# SubHarmonics_Control_Board_v1.net
KiCad netlist of a schematic drawn in EAGLE
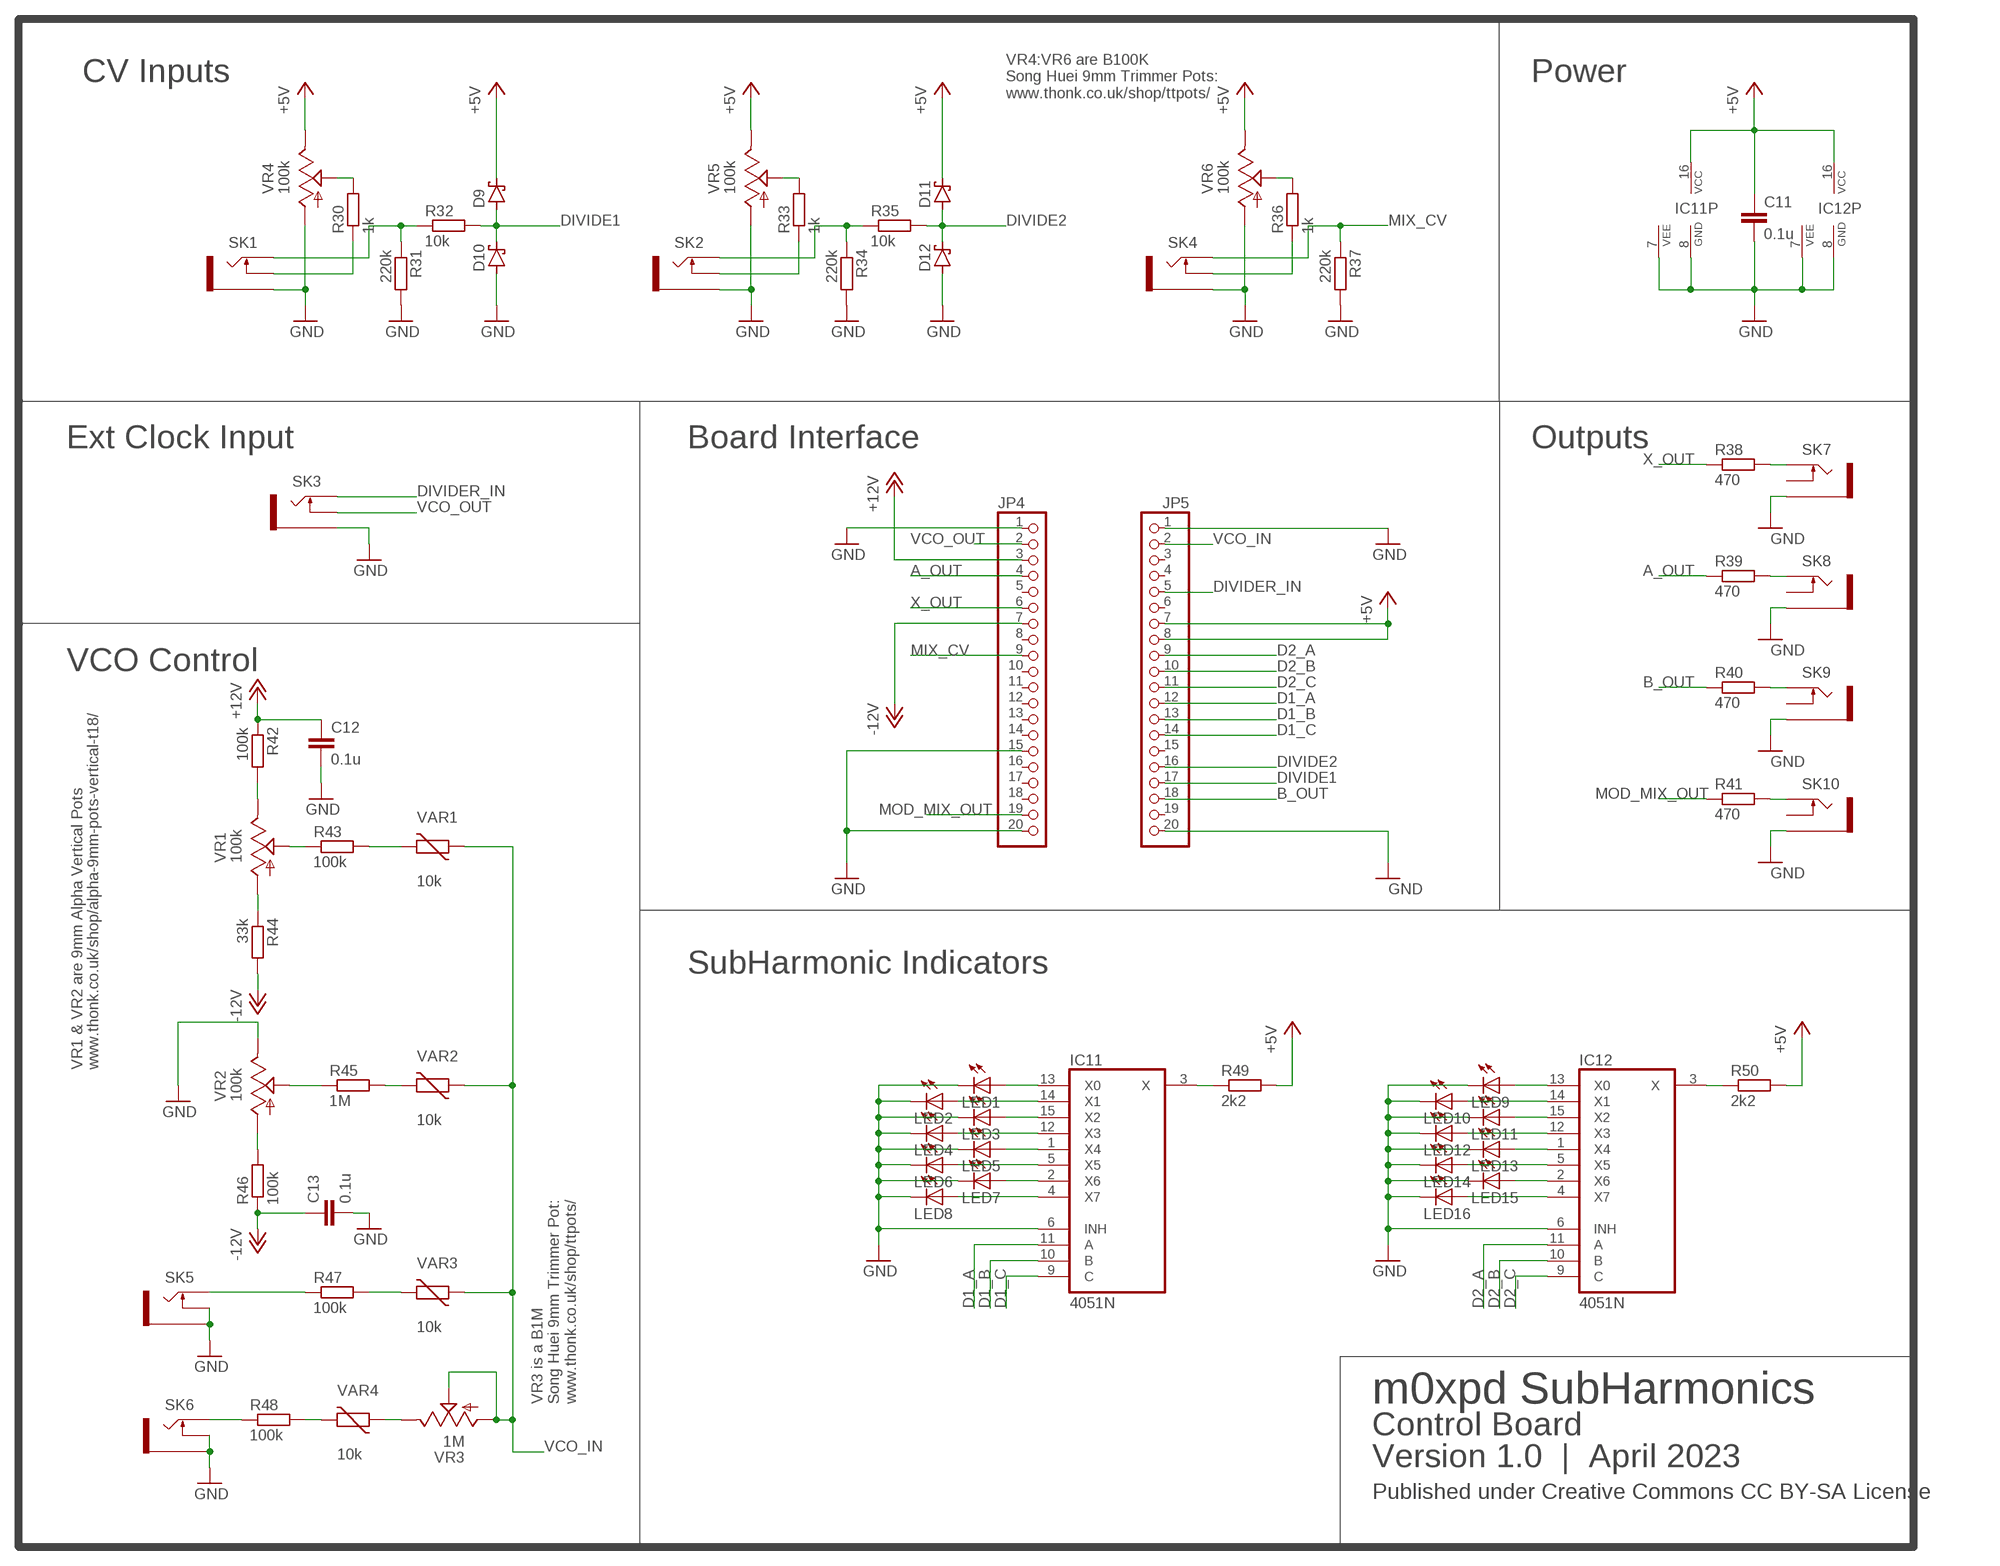
[diagram p0: schematic, sheet 1]

(export (version "E")
  (design (tool "Eeschema 10.0.6"))
  (components
    (comp (ref "C11")
      (value "0.1u")
      (footprint "eagle-import:C050-025X075")
      (libsource (lib "eagle-import") (part "C-EU050-025X075"))
    )
    (comp (ref "C12")
      (value "0.1u")
      (footprint "eagle-import:C050-025X075")
      (libsource (lib "eagle-import") (part "C-EU050-025X075"))
    )
    (comp (ref "C13")
      (value "0.1u")
      (footprint "eagle-import:C050-025X075")
      (libsource (lib "eagle-import") (part "C-EU050-025X075"))
    )
    (comp (ref "D9")
      (value "1N5817-T")
      (footprint "eagle-import:DO41-7.6")
      (libsource (lib "eagle-import") (part "1N5817-T"))
    )
    (comp (ref "D10")
      (value "1N5817-T")
      (footprint "eagle-import:DO41-7.6")
      (libsource (lib "eagle-import") (part "1N5817-T"))
    )
    (comp (ref "D11")
      (value "1N5817-T")
      (footprint "eagle-import:DO41-7.6")
      (libsource (lib "eagle-import") (part "1N5817-T"))
    )
    (comp (ref "D12")
      (value "1N5817-T")
      (footprint "eagle-import:DO41-7.6")
      (libsource (lib "eagle-import") (part "1N5817-T"))
    )
    (comp (ref "IC11")
      (value "4051N")
      (footprint "eagle-import:DIL16")
      (libsource (lib "eagle-import") (part "4051N"))
    )
    (comp (ref "IC12")
      (value "4051N")
      (footprint "eagle-import:DIL16")
      (libsource (lib "eagle-import") (part "4051N"))
    )
    (comp (ref "JP4")
      (value "PINHD-1X20")
      (footprint "eagle-import:1X20")
      (libsource (lib "eagle-import") (part "PINHD-1X20"))
    )
    (comp (ref "JP5")
      (value "PINHD-1X20")
      (footprint "eagle-import:1X20")
      (libsource (lib "eagle-import") (part "PINHD-1X20"))
    )
    (comp (ref "LED1")
      (value "LED3MM")
      (footprint "eagle-import:LED3MM")
      (libsource (lib "eagle-import") (part "LED3MM"))
    )
    (comp (ref "LED2")
      (value "LED3MM")
      (footprint "eagle-import:LED3MM")
      (libsource (lib "eagle-import") (part "LED3MM"))
    )
    (comp (ref "LED3")
      (value "LED3MM")
      (footprint "eagle-import:LED3MM")
      (libsource (lib "eagle-import") (part "LED3MM"))
    )
    (comp (ref "LED4")
      (value "LED3MM")
      (footprint "eagle-import:LED3MM")
      (libsource (lib "eagle-import") (part "LED3MM"))
    )
    (comp (ref "LED5")
      (value "LED3MM")
      (footprint "eagle-import:LED3MM")
      (libsource (lib "eagle-import") (part "LED3MM"))
    )
    (comp (ref "LED6")
      (value "LED3MM")
      (footprint "eagle-import:LED3MM")
      (libsource (lib "eagle-import") (part "LED3MM"))
    )
    (comp (ref "LED7")
      (value "LED3MM")
      (footprint "eagle-import:LED3MM")
      (libsource (lib "eagle-import") (part "LED3MM"))
    )
    (comp (ref "LED8")
      (value "LED3MM")
      (footprint "eagle-import:LED3MM")
      (libsource (lib "eagle-import") (part "LED3MM"))
    )
    (comp (ref "LED9")
      (value "LED3MM")
      (footprint "eagle-import:LED3MM")
      (libsource (lib "eagle-import") (part "LED3MM"))
    )
    (comp (ref "LED10")
      (value "LED3MM")
      (footprint "eagle-import:LED3MM")
      (libsource (lib "eagle-import") (part "LED3MM"))
    )
    (comp (ref "LED11")
      (value "LED3MM")
      (footprint "eagle-import:LED3MM")
      (libsource (lib "eagle-import") (part "LED3MM"))
    )
    (comp (ref "LED12")
      (value "LED3MM")
      (footprint "eagle-import:LED3MM")
      (libsource (lib "eagle-import") (part "LED3MM"))
    )
    (comp (ref "LED13")
      (value "LED3MM")
      (footprint "eagle-import:LED3MM")
      (libsource (lib "eagle-import") (part "LED3MM"))
    )
    (comp (ref "LED14")
      (value "LED3MM")
      (footprint "eagle-import:LED3MM")
      (libsource (lib "eagle-import") (part "LED3MM"))
    )
    (comp (ref "LED15")
      (value "LED3MM")
      (footprint "eagle-import:LED3MM")
      (libsource (lib "eagle-import") (part "LED3MM"))
    )
    (comp (ref "LED16")
      (value "LED3MM")
      (footprint "eagle-import:LED3MM")
      (libsource (lib "eagle-import") (part "LED3MM"))
    )
    (comp (ref "R30")
      (value "1k")
      (footprint "eagle-import:0204_7")
      (libsource (lib "eagle-import") (part "R-EU_0204/7"))
    )
    (comp (ref "R31")
      (value "220k")
      (footprint "eagle-import:0204_7")
      (libsource (lib "eagle-import") (part "R-EU_0204/7"))
    )
    (comp (ref "R32")
      (value "10k")
      (footprint "eagle-import:0204_7")
      (libsource (lib "eagle-import") (part "R-EU_0204/7"))
    )
    (comp (ref "R33")
      (value "1k")
      (footprint "eagle-import:0204_7")
      (libsource (lib "eagle-import") (part "R-EU_0204/7"))
    )
    (comp (ref "R34")
      (value "220k")
      (footprint "eagle-import:0204_7")
      (libsource (lib "eagle-import") (part "R-EU_0204/7"))
    )
    (comp (ref "R35")
      (value "10k")
      (footprint "eagle-import:0204_7")
      (libsource (lib "eagle-import") (part "R-EU_0204/7"))
    )
    (comp (ref "R36")
      (value "1k")
      (footprint "eagle-import:0204_7")
      (libsource (lib "eagle-import") (part "R-EU_0204/7"))
    )
    (comp (ref "R37")
      (value "220k")
      (footprint "eagle-import:0204_7")
      (libsource (lib "eagle-import") (part "R-EU_0204/7"))
    )
    (comp (ref "R38")
      (value "470")
      (footprint "eagle-import:0204_7")
      (libsource (lib "eagle-import") (part "R-EU_0204/7"))
    )
    (comp (ref "R39")
      (value "470")
      (footprint "eagle-import:0204_7")
      (libsource (lib "eagle-import") (part "R-EU_0204/7"))
    )
    (comp (ref "R40")
      (value "470")
      (footprint "eagle-import:0204_7")
      (libsource (lib "eagle-import") (part "R-EU_0204/7"))
    )
    (comp (ref "R41")
      (value "470")
      (footprint "eagle-import:0204_7")
      (libsource (lib "eagle-import") (part "R-EU_0204/7"))
    )
    (comp (ref "R42")
      (value "100k")
      (footprint "eagle-import:0204_7")
      (libsource (lib "eagle-import") (part "R-EU_0204/7"))
    )
    (comp (ref "R43")
      (value "100k")
      (footprint "eagle-import:0204_7")
      (libsource (lib "eagle-import") (part "R-EU_0204/7"))
    )
    (comp (ref "R44")
      (value "33k")
      (footprint "eagle-import:0204_7")
      (libsource (lib "eagle-import") (part "R-EU_0204/7"))
    )
    (comp (ref "R45")
      (value "1M")
      (footprint "eagle-import:0204_7")
      (libsource (lib "eagle-import") (part "R-EU_0204/7"))
    )
    (comp (ref "R46")
      (value "100k")
      (footprint "eagle-import:0204_7")
      (libsource (lib "eagle-import") (part "R-EU_0204/7"))
    )
    (comp (ref "R47")
      (value "100k")
      (footprint "eagle-import:0204_7")
      (libsource (lib "eagle-import") (part "R-EU_0204/7"))
    )
    (comp (ref "R48")
      (value "100k")
      (footprint "eagle-import:0204_7")
      (libsource (lib "eagle-import") (part "R-EU_0204/7"))
    )
    (comp (ref "R49")
      (value "2k2")
      (footprint "eagle-import:0204_7")
      (libsource (lib "eagle-import") (part "R-EU_0204/7"))
    )
    (comp (ref "R50")
      (value "2k2")
      (footprint "eagle-import:0204_7")
      (libsource (lib "eagle-import") (part "R-EU_0204/7"))
    )
    (comp (ref "SK1")
      (value "THONKICONN_JACK")
      (footprint "eagle-import:WQP-PJ301M-12_JACK")
      (libsource (lib "eagle-import") (part "THONKICONN_JACK"))
    )
    (comp (ref "SK2")
      (value "THONKICONN_JACK")
      (footprint "eagle-import:WQP-PJ301M-12_JACK")
      (libsource (lib "eagle-import") (part "THONKICONN_JACK"))
    )
    (comp (ref "SK3")
      (value "THONKICONN_JACK")
      (footprint "eagle-import:WQP-PJ301M-12_JACK")
      (libsource (lib "eagle-import") (part "THONKICONN_JACK"))
    )
    (comp (ref "SK4")
      (value "THONKICONN_JACK")
      (footprint "eagle-import:WQP-PJ301M-12_JACK")
      (libsource (lib "eagle-import") (part "THONKICONN_JACK"))
    )
    (comp (ref "SK5")
      (value "THONKICONN_JACK")
      (footprint "eagle-import:WQP-PJ301M-12_JACK")
      (libsource (lib "eagle-import") (part "THONKICONN_JACK"))
    )
    (comp (ref "SK6")
      (value "THONKICONN_JACK")
      (footprint "eagle-import:WQP-PJ301M-12_JACK")
      (libsource (lib "eagle-import") (part "THONKICONN_JACK"))
    )
    (comp (ref "SK7")
      (value "THONKICONN_JACK")
      (footprint "eagle-import:WQP-PJ301M-12_JACK")
      (libsource (lib "eagle-import") (part "THONKICONN_JACK"))
    )
    (comp (ref "SK8")
      (value "THONKICONN_JACK")
      (footprint "eagle-import:WQP-PJ301M-12_JACK")
      (libsource (lib "eagle-import") (part "THONKICONN_JACK"))
    )
    (comp (ref "SK9")
      (value "THONKICONN_JACK")
      (footprint "eagle-import:WQP-PJ301M-12_JACK")
      (libsource (lib "eagle-import") (part "THONKICONN_JACK"))
    )
    (comp (ref "SK10")
      (value "THONKICONN_JACK")
      (footprint "eagle-import:WQP-PJ301M-12_JACK")
      (libsource (lib "eagle-import") (part "THONKICONN_JACK"))
    )
    (comp (ref "VAR1")
      (value "10k")
      (footprint "eagle-import:C025-024X044")
      (libsource (lib "eagle-import") (part "VARISTOR"))
    )
    (comp (ref "VAR2")
      (value "10k")
      (footprint "eagle-import:C025-024X044")
      (libsource (lib "eagle-import") (part "VARISTOR"))
    )
    (comp (ref "VAR3")
      (value "10k")
      (footprint "eagle-import:C025-024X044")
      (libsource (lib "eagle-import") (part "VARISTOR"))
    )
    (comp (ref "VAR4")
      (value "10k")
      (footprint "eagle-import:C025-024X044")
      (libsource (lib "eagle-import") (part "VARISTOR"))
    )
    (comp (ref "VR1")
      (value "100k")
      (footprint "eagle-import:9MM_SNAP-IN_POT")
      (libsource (lib "eagle-import") (part "9MM_SNAP-IN_POT_"))
    )
    (comp (ref "VR2")
      (value "100k")
      (footprint "eagle-import:9MM_SNAP-IN_POT")
      (libsource (lib "eagle-import") (part "9MM_SNAP-IN_POT_"))
    )
    (comp (ref "VR3")
      (value "1M")
      (footprint "eagle-import:9MM_SNAP-IN_POT")
      (libsource (lib "eagle-import") (part "9MM_SNAP-IN_POT_"))
    )
    (comp (ref "VR4")
      (value "100k")
      (footprint "eagle-import:9MM_SNAP-IN_POT")
      (libsource (lib "eagle-import") (part "9MM_SNAP-IN_POT_"))
    )
    (comp (ref "VR5")
      (value "100k")
      (footprint "eagle-import:9MM_SNAP-IN_POT")
      (libsource (lib "eagle-import") (part "9MM_SNAP-IN_POT_"))
    )
    (comp (ref "VR6")
      (value "100k")
      (footprint "eagle-import:9MM_SNAP-IN_POT")
      (libsource (lib "eagle-import") (part "9MM_SNAP-IN_POT_"))
    )
  )
  (nets
    (net (code "1") (name "+5V") (class "Default")
      (node (ref "C11") (pin "1") (pinfunction "1_1") (pintype "passive"))
      (node (ref "D11") (pin "C") (pinfunction "C_C") (pintype "passive"))
      (node (ref "D9") (pin "C") (pinfunction "C_C") (pintype "passive"))
      (node (ref "IC11") (pin "16") (pinfunction "VCC_16") (pintype "power_in"))
      (node (ref "IC12") (pin "16") (pinfunction "VCC_16") (pintype "power_in"))
      (node (ref "JP5") (pin "7") (pinfunction "7_7") (pintype "passive"))
      (node (ref "JP5") (pin "8") (pinfunction "8_8") (pintype "passive"))
      (node (ref "R49") (pin "2") (pinfunction "2_2") (pintype "passive"))
      (node (ref "R50") (pin "2") (pinfunction "2_2") (pintype "passive"))
      (node (ref "VR4") (pin "3") (pinfunction "E_3") (pintype "passive"))
      (node (ref "VR5") (pin "3") (pinfunction "E_3") (pintype "passive"))
      (node (ref "VR6") (pin "3") (pinfunction "E_3") (pintype "passive"))
    )
    (net (code "2") (name "+12V") (class "Default")
      (node (ref "C12") (pin "1") (pinfunction "1_1") (pintype "passive"))
      (node (ref "JP4") (pin "3") (pinfunction "3_3") (pintype "passive"))
      (node (ref "R42") (pin "1") (pinfunction "1_1") (pintype "passive"))
    )
    (net (code "3") (name "-12V") (class "Default")
      (node (ref "C13") (pin "1") (pinfunction "1_1") (pintype "passive"))
      (node (ref "JP4") (pin "7") (pinfunction "7_7") (pintype "passive"))
      (node (ref "R44") (pin "2") (pinfunction "2_2") (pintype "passive"))
      (node (ref "R46") (pin "1") (pinfunction "1_1") (pintype "passive"))
    )
    (net (code "4") (name "/A_OUT") (class "Default")
      (node (ref "JP4") (pin "4") (pinfunction "4_4") (pintype "passive"))
      (node (ref "R39") (pin "1") (pinfunction "1_1") (pintype "passive"))
    )
    (net (code "5") (name "/B_OUT") (class "Default")
      (node (ref "JP5") (pin "18") (pinfunction "18_18") (pintype "passive"))
      (node (ref "R40") (pin "1") (pinfunction "1_1") (pintype "passive"))
    )
    (net (code "6") (name "/D1_A") (class "Default")
      (node (ref "IC11") (pin "11") (pinfunction "A_11") (pintype "input"))
      (node (ref "JP5") (pin "12") (pinfunction "12_12") (pintype "passive"))
    )
    (net (code "7") (name "/D1_B") (class "Default")
      (node (ref "IC11") (pin "10") (pinfunction "B_10") (pintype "input"))
      (node (ref "JP5") (pin "13") (pinfunction "13_13") (pintype "passive"))
    )
    (net (code "8") (name "/D1_C") (class "Default")
      (node (ref "IC11") (pin "9") (pinfunction "C_9") (pintype "input"))
      (node (ref "JP5") (pin "14") (pinfunction "14_14") (pintype "passive"))
    )
    (net (code "9") (name "/D2_A") (class "Default")
      (node (ref "IC12") (pin "11") (pinfunction "A_11") (pintype "input"))
      (node (ref "JP5") (pin "9") (pinfunction "9_9") (pintype "passive"))
    )
    (net (code "10") (name "/D2_B") (class "Default")
      (node (ref "IC12") (pin "10") (pinfunction "B_10") (pintype "input"))
      (node (ref "JP5") (pin "10") (pinfunction "10_10") (pintype "passive"))
    )
    (net (code "11") (name "/D2_C") (class "Default")
      (node (ref "IC12") (pin "9") (pinfunction "C_9") (pintype "input"))
      (node (ref "JP5") (pin "11") (pinfunction "11_11") (pintype "passive"))
    )
    (net (code "12") (name "/DIVIDE1") (class "Default")
      (node (ref "D10") (pin "C") (pinfunction "C_C") (pintype "passive"))
      (node (ref "D9") (pin "A") (pinfunction "A_A") (pintype "passive"))
      (node (ref "JP5") (pin "17") (pinfunction "17_17") (pintype "passive"))
      (node (ref "R32") (pin "2") (pinfunction "2_2") (pintype "passive"))
    )
    (net (code "13") (name "/DIVIDE2") (class "Default")
      (node (ref "D11") (pin "A") (pinfunction "A_A") (pintype "passive"))
      (node (ref "D12") (pin "C") (pinfunction "C_C") (pintype "passive"))
      (node (ref "JP5") (pin "16") (pinfunction "16_16") (pintype "passive"))
      (node (ref "R35") (pin "2") (pinfunction "2_2") (pintype "passive"))
    )
    (net (code "14") (name "/DIVIDER_IN") (class "Default")
      (node (ref "JP5") (pin "5") (pinfunction "5_5") (pintype "passive"))
      (node (ref "SK3") (pin "P$1_TIP") (pinfunction "TIP_P$1_TIP") (pintype "passive"))
    )
    (net (code "15") (name "/MIX_CV") (class "Default")
      (node (ref "JP4") (pin "9") (pinfunction "9_9") (pintype "passive"))
      (node (ref "R37") (pin "1") (pinfunction "1_1") (pintype "passive"))
      (node (ref "SK4") (pin "P$1_TIP") (pinfunction "TIP_P$1_TIP") (pintype "passive"))
    )
    (net (code "16") (name "/MOD_MIX_OUT") (class "Default")
      (node (ref "JP4") (pin "19") (pinfunction "19_19") (pintype "passive"))
      (node (ref "R41") (pin "1") (pinfunction "1_1") (pintype "passive"))
    )
    (net (code "17") (name "/VCO_IN") (class "Default")
      (node (ref "JP5") (pin "2") (pinfunction "2_2") (pintype "passive"))
      (node (ref "VAR1") (pin "1") (pinfunction "1_1") (pintype "passive"))
      (node (ref "VAR2") (pin "1") (pinfunction "1_1") (pintype "passive"))
      (node (ref "VAR3") (pin "1") (pinfunction "1_1") (pintype "passive"))
      (node (ref "VR3") (pin "1") (pinfunction "A_1") (pintype "passive"))
      (node (ref "VR3") (pin "2") (pinfunction "S_2") (pintype "passive"))
    )
    (net (code "18") (name "/VCO_OUT") (class "Default")
      (node (ref "JP4") (pin "2") (pinfunction "2_2") (pintype "passive"))
      (node (ref "SK3") (pin "P$2_SWITCH") (pinfunction "SWITCH_P$2_SWITCH") (pintype "passive"))
    )
    (net (code "19") (name "/X_OUT") (class "Default")
      (node (ref "JP4") (pin "6") (pinfunction "6_6") (pintype "passive"))
      (node (ref "R38") (pin "1") (pinfunction "1_1") (pintype "passive"))
    )
    (net (code "20") (name "GND") (class "Default")
      (node (ref "C11") (pin "2") (pinfunction "2_2") (pintype "passive"))
      (node (ref "C12") (pin "2") (pinfunction "2_2") (pintype "passive"))
      (node (ref "C13") (pin "2") (pinfunction "2_2") (pintype "passive"))
      (node (ref "D10") (pin "A") (pinfunction "A_A") (pintype "passive"))
      (node (ref "D12") (pin "A") (pinfunction "A_A") (pintype "passive"))
      (node (ref "IC11") (pin "6") (pinfunction "INH_6") (pintype "input"))
      (node (ref "IC11") (pin "7") (pinfunction "VEE_7") (pintype "power_in"))
      (node (ref "IC11") (pin "8") (pinfunction "GND_8") (pintype "power_in"))
      (node (ref "IC12") (pin "6") (pinfunction "INH_6") (pintype "input"))
      (node (ref "IC12") (pin "7") (pinfunction "VEE_7") (pintype "power_in"))
      (node (ref "IC12") (pin "8") (pinfunction "GND_8") (pintype "power_in"))
      (node (ref "JP4") (pin "1") (pinfunction "1_1") (pintype "passive"))
      (node (ref "JP4") (pin "15") (pinfunction "15_15") (pintype "passive"))
      (node (ref "JP4") (pin "20") (pinfunction "20_20") (pintype "passive"))
      (node (ref "JP5") (pin "1") (pinfunction "1_1") (pintype "passive"))
      (node (ref "JP5") (pin "20") (pinfunction "20_20") (pintype "passive"))
      (node (ref "LED1") (pin "K") (pinfunction "C_K") (pintype "passive"))
      (node (ref "LED10") (pin "K") (pinfunction "C_K") (pintype "passive"))
      (node (ref "LED11") (pin "K") (pinfunction "C_K") (pintype "passive"))
      (node (ref "LED12") (pin "K") (pinfunction "C_K") (pintype "passive"))
      (node (ref "LED13") (pin "K") (pinfunction "C_K") (pintype "passive"))
      (node (ref "LED14") (pin "K") (pinfunction "C_K") (pintype "passive"))
      (node (ref "LED15") (pin "K") (pinfunction "C_K") (pintype "passive"))
      (node (ref "LED16") (pin "K") (pinfunction "C_K") (pintype "passive"))
      (node (ref "LED2") (pin "K") (pinfunction "C_K") (pintype "passive"))
      (node (ref "LED3") (pin "K") (pinfunction "C_K") (pintype "passive"))
      (node (ref "LED4") (pin "K") (pinfunction "C_K") (pintype "passive"))
      (node (ref "LED5") (pin "K") (pinfunction "C_K") (pintype "passive"))
      (node (ref "LED6") (pin "K") (pinfunction "C_K") (pintype "passive"))
      (node (ref "LED7") (pin "K") (pinfunction "C_K") (pintype "passive"))
      (node (ref "LED8") (pin "K") (pinfunction "C_K") (pintype "passive"))
      (node (ref "LED9") (pin "K") (pinfunction "C_K") (pintype "passive"))
      (node (ref "R31") (pin "2") (pinfunction "2_2") (pintype "passive"))
      (node (ref "R34") (pin "2") (pinfunction "2_2") (pintype "passive"))
      (node (ref "R37") (pin "2") (pinfunction "2_2") (pintype "passive"))
      (node (ref "SK1") (pin "P$3_SLEEVE") (pinfunction "SLEEVE_P$3_SLEEVE") (pintype "passive"))
      (node (ref "SK10") (pin "P$3_SLEEVE") (pinfunction "SLEEVE_P$3_SLEEVE") (pintype "passive"))
      (node (ref "SK2") (pin "P$3_SLEEVE") (pinfunction "SLEEVE_P$3_SLEEVE") (pintype "passive"))
      (node (ref "SK3") (pin "P$3_SLEEVE") (pinfunction "SLEEVE_P$3_SLEEVE") (pintype "passive"))
      (node (ref "SK4") (pin "P$3_SLEEVE") (pinfunction "SLEEVE_P$3_SLEEVE") (pintype "passive"))
      (node (ref "SK5") (pin "P$2_SWITCH") (pinfunction "SWITCH_P$2_SWITCH") (pintype "passive"))
      (node (ref "SK5") (pin "P$3_SLEEVE") (pinfunction "SLEEVE_P$3_SLEEVE") (pintype "passive"))
      (node (ref "SK6") (pin "P$2_SWITCH") (pinfunction "SWITCH_P$2_SWITCH") (pintype "passive"))
      (node (ref "SK6") (pin "P$3_SLEEVE") (pinfunction "SLEEVE_P$3_SLEEVE") (pintype "passive"))
      (node (ref "SK7") (pin "P$3_SLEEVE") (pinfunction "SLEEVE_P$3_SLEEVE") (pintype "passive"))
      (node (ref "SK8") (pin "P$3_SLEEVE") (pinfunction "SLEEVE_P$3_SLEEVE") (pintype "passive"))
      (node (ref "SK9") (pin "P$3_SLEEVE") (pinfunction "SLEEVE_P$3_SLEEVE") (pintype "passive"))
      (node (ref "VR2") (pin "3") (pinfunction "E_3") (pintype "passive"))
      (node (ref "VR4") (pin "1") (pinfunction "A_1") (pintype "passive"))
      (node (ref "VR5") (pin "1") (pinfunction "A_1") (pintype "passive"))
      (node (ref "VR6") (pin "1") (pinfunction "A_1") (pintype "passive"))
    )
    (net (code "21") (name "Net-(IC11A-X)") (class "Default")
      (node (ref "IC11") (pin "3") (pinfunction "X_3") (pintype "bidirectional"))
      (node (ref "R49") (pin "1") (pinfunction "1_1") (pintype "passive"))
    )
    (net (code "22") (name "Net-(IC11A-X0)") (class "Default")
      (node (ref "IC11") (pin "13") (pinfunction "X0_13") (pintype "bidirectional"))
      (node (ref "LED1") (pin "A") (pinfunction "A_A") (pintype "passive"))
    )
    (net (code "23") (name "Net-(IC11A-X1)") (class "Default")
      (node (ref "IC11") (pin "14") (pinfunction "X1_14") (pintype "bidirectional"))
      (node (ref "LED2") (pin "A") (pinfunction "A_A") (pintype "passive"))
    )
    (net (code "24") (name "Net-(IC11A-X2)") (class "Default")
      (node (ref "IC11") (pin "15") (pinfunction "X2_15") (pintype "bidirectional"))
      (node (ref "LED3") (pin "A") (pinfunction "A_A") (pintype "passive"))
    )
    (net (code "25") (name "Net-(IC11A-X3)") (class "Default")
      (node (ref "IC11") (pin "12") (pinfunction "X3_12") (pintype "bidirectional"))
      (node (ref "LED4") (pin "A") (pinfunction "A_A") (pintype "passive"))
    )
    (net (code "26") (name "Net-(IC11A-X4)") (class "Default")
      (node (ref "IC11") (pin "1") (pinfunction "X4_1") (pintype "bidirectional"))
      (node (ref "LED5") (pin "A") (pinfunction "A_A") (pintype "passive"))
    )
    (net (code "27") (name "Net-(IC11A-X5)") (class "Default")
      (node (ref "IC11") (pin "5") (pinfunction "X5_5") (pintype "bidirectional"))
      (node (ref "LED6") (pin "A") (pinfunction "A_A") (pintype "passive"))
    )
    (net (code "28") (name "Net-(IC11A-X6)") (class "Default")
      (node (ref "IC11") (pin "2") (pinfunction "X6_2") (pintype "bidirectional"))
      (node (ref "LED7") (pin "A") (pinfunction "A_A") (pintype "passive"))
    )
    (net (code "29") (name "Net-(IC11A-X7)") (class "Default")
      (node (ref "IC11") (pin "4") (pinfunction "X7_4") (pintype "bidirectional"))
      (node (ref "LED8") (pin "A") (pinfunction "A_A") (pintype "passive"))
    )
    (net (code "30") (name "Net-(IC12A-X)") (class "Default")
      (node (ref "IC12") (pin "3") (pinfunction "X_3") (pintype "bidirectional"))
      (node (ref "R50") (pin "1") (pinfunction "1_1") (pintype "passive"))
    )
    (net (code "31") (name "Net-(IC12A-X0)") (class "Default")
      (node (ref "IC12") (pin "13") (pinfunction "X0_13") (pintype "bidirectional"))
      (node (ref "LED9") (pin "A") (pinfunction "A_A") (pintype "passive"))
    )
    (net (code "32") (name "Net-(IC12A-X1)") (class "Default")
      (node (ref "IC12") (pin "14") (pinfunction "X1_14") (pintype "bidirectional"))
      (node (ref "LED10") (pin "A") (pinfunction "A_A") (pintype "passive"))
    )
    (net (code "33") (name "Net-(IC12A-X2)") (class "Default")
      (node (ref "IC12") (pin "15") (pinfunction "X2_15") (pintype "bidirectional"))
      (node (ref "LED11") (pin "A") (pinfunction "A_A") (pintype "passive"))
    )
    (net (code "34") (name "Net-(IC12A-X3)") (class "Default")
      (node (ref "IC12") (pin "12") (pinfunction "X3_12") (pintype "bidirectional"))
      (node (ref "LED12") (pin "A") (pinfunction "A_A") (pintype "passive"))
    )
    (net (code "35") (name "Net-(IC12A-X4)") (class "Default")
      (node (ref "IC12") (pin "1") (pinfunction "X4_1") (pintype "bidirectional"))
      (node (ref "LED13") (pin "A") (pinfunction "A_A") (pintype "passive"))
    )
    (net (code "36") (name "Net-(IC12A-X5)") (class "Default")
      (node (ref "IC12") (pin "5") (pinfunction "X5_5") (pintype "bidirectional"))
      (node (ref "LED14") (pin "A") (pinfunction "A_A") (pintype "passive"))
    )
    (net (code "37") (name "Net-(IC12A-X6)") (class "Default")
      (node (ref "IC12") (pin "2") (pinfunction "X6_2") (pintype "bidirectional"))
      (node (ref "LED15") (pin "A") (pinfunction "A_A") (pintype "passive"))
    )
    (net (code "38") (name "Net-(IC12A-X7)") (class "Default")
      (node (ref "IC12") (pin "4") (pinfunction "X7_4") (pintype "bidirectional"))
      (node (ref "LED16") (pin "A") (pinfunction "A_A") (pintype "passive"))
    )
    (net (code "39") (name "Net-(R43-Pad2)") (class "Default")
      (node (ref "R43") (pin "2") (pinfunction "2_2") (pintype "passive"))
      (node (ref "VAR1") (pin "2") (pinfunction "2_2") (pintype "passive"))
    )
    (net (code "40") (name "Net-(R45-Pad2)") (class "Default")
      (node (ref "R45") (pin "2") (pinfunction "2_2") (pintype "passive"))
      (node (ref "VAR2") (pin "2") (pinfunction "2_2") (pintype "passive"))
    )
    (net (code "41") (name "Net-(R47-Pad2)") (class "Default")
      (node (ref "R47") (pin "2") (pinfunction "2_2") (pintype "passive"))
      (node (ref "VAR3") (pin "2") (pinfunction "2_2") (pintype "passive"))
    )
    (net (code "42") (name "Net-(R48-Pad2)") (class "Default")
      (node (ref "R48") (pin "2") (pinfunction "2_2") (pintype "passive"))
      (node (ref "VAR4") (pin "2") (pinfunction "2_2") (pintype "passive"))
    )
    (net (code "43") (name "Net-(SK1-SWITCH)") (class "Default")
      (node (ref "R30") (pin "1") (pinfunction "1_1") (pintype "passive"))
      (node (ref "SK1") (pin "P$2_SWITCH") (pinfunction "SWITCH_P$2_SWITCH") (pintype "passive"))
    )
    (net (code "44") (name "Net-(SK1-TIP)") (class "Default")
      (node (ref "R31") (pin "1") (pinfunction "1_1") (pintype "passive"))
      (node (ref "R32") (pin "1") (pinfunction "1_1") (pintype "passive"))
      (node (ref "SK1") (pin "P$1_TIP") (pinfunction "TIP_P$1_TIP") (pintype "passive"))
    )
    (net (code "45") (name "Net-(SK2-SWITCH)") (class "Default")
      (node (ref "R33") (pin "1") (pinfunction "1_1") (pintype "passive"))
      (node (ref "SK2") (pin "P$2_SWITCH") (pinfunction "SWITCH_P$2_SWITCH") (pintype "passive"))
    )
    (net (code "46") (name "Net-(SK2-TIP)") (class "Default")
      (node (ref "R34") (pin "1") (pinfunction "1_1") (pintype "passive"))
      (node (ref "R35") (pin "1") (pinfunction "1_1") (pintype "passive"))
      (node (ref "SK2") (pin "P$1_TIP") (pinfunction "TIP_P$1_TIP") (pintype "passive"))
    )
    (net (code "47") (name "Net-(SK4-SWITCH)") (class "Default")
      (node (ref "R36") (pin "1") (pinfunction "1_1") (pintype "passive"))
      (node (ref "SK4") (pin "P$2_SWITCH") (pinfunction "SWITCH_P$2_SWITCH") (pintype "passive"))
    )
    (net (code "48") (name "Net-(SK5-TIP)") (class "Default")
      (node (ref "R47") (pin "1") (pinfunction "1_1") (pintype "passive"))
      (node (ref "SK5") (pin "P$1_TIP") (pinfunction "TIP_P$1_TIP") (pintype "passive"))
    )
    (net (code "49") (name "Net-(SK6-TIP)") (class "Default")
      (node (ref "R48") (pin "1") (pinfunction "1_1") (pintype "passive"))
      (node (ref "SK6") (pin "P$1_TIP") (pinfunction "TIP_P$1_TIP") (pintype "passive"))
    )
    (net (code "50") (name "Net-(SK7-TIP)") (class "Default")
      (node (ref "R38") (pin "2") (pinfunction "2_2") (pintype "passive"))
      (node (ref "SK7") (pin "P$1_TIP") (pinfunction "TIP_P$1_TIP") (pintype "passive"))
    )
    (net (code "51") (name "Net-(SK8-TIP)") (class "Default")
      (node (ref "R39") (pin "2") (pinfunction "2_2") (pintype "passive"))
      (node (ref "SK8") (pin "P$1_TIP") (pinfunction "TIP_P$1_TIP") (pintype "passive"))
    )
    (net (code "52") (name "Net-(SK9-TIP)") (class "Default")
      (node (ref "R40") (pin "2") (pinfunction "2_2") (pintype "passive"))
      (node (ref "SK9") (pin "P$1_TIP") (pinfunction "TIP_P$1_TIP") (pintype "passive"))
    )
    (net (code "53") (name "Net-(SK10-TIP)") (class "Default")
      (node (ref "R41") (pin "2") (pinfunction "2_2") (pintype "passive"))
      (node (ref "SK10") (pin "P$1_TIP") (pinfunction "TIP_P$1_TIP") (pintype "passive"))
    )
    (net (code "54") (name "Net-(VR1-A)") (class "Default")
      (node (ref "R44") (pin "1") (pinfunction "1_1") (pintype "passive"))
      (node (ref "VR1") (pin "1") (pinfunction "A_1") (pintype "passive"))
    )
    (net (code "55") (name "Net-(VR1-E)") (class "Default")
      (node (ref "R42") (pin "2") (pinfunction "2_2") (pintype "passive"))
      (node (ref "VR1") (pin "3") (pinfunction "E_3") (pintype "passive"))
    )
    (net (code "56") (name "Net-(VR1-S)") (class "Default")
      (node (ref "R43") (pin "1") (pinfunction "1_1") (pintype "passive"))
      (node (ref "VR1") (pin "2") (pinfunction "S_2") (pintype "passive"))
    )
    (net (code "57") (name "Net-(VR2-A)") (class "Default")
      (node (ref "R46") (pin "2") (pinfunction "2_2") (pintype "passive"))
      (node (ref "VR2") (pin "1") (pinfunction "A_1") (pintype "passive"))
    )
    (net (code "58") (name "Net-(VR2-S)") (class "Default")
      (node (ref "R45") (pin "1") (pinfunction "1_1") (pintype "passive"))
      (node (ref "VR2") (pin "2") (pinfunction "S_2") (pintype "passive"))
    )
    (net (code "59") (name "Net-(VR3-E)") (class "Default")
      (node (ref "VAR4") (pin "1") (pinfunction "1_1") (pintype "passive"))
      (node (ref "VR3") (pin "3") (pinfunction "E_3") (pintype "passive"))
    )
    (net (code "60") (name "Net-(VR4-S)") (class "Default")
      (node (ref "R30") (pin "2") (pinfunction "2_2") (pintype "passive"))
      (node (ref "VR4") (pin "2") (pinfunction "S_2") (pintype "passive"))
    )
    (net (code "61") (name "Net-(VR5-S)") (class "Default")
      (node (ref "R33") (pin "2") (pinfunction "2_2") (pintype "passive"))
      (node (ref "VR5") (pin "2") (pinfunction "S_2") (pintype "passive"))
    )
    (net (code "62") (name "Net-(VR6-S)") (class "Default")
      (node (ref "R36") (pin "2") (pinfunction "2_2") (pintype "passive"))
      (node (ref "VR6") (pin "2") (pinfunction "S_2") (pintype "passive"))
    )
    (net (code "63") (name "unconnected-(JP4-Pad5)") (class "Default")
      (node (ref "JP4") (pin "5") (pinfunction "5_5") (pintype "passive"))
    )
    (net (code "64") (name "unconnected-(JP4-Pad8)") (class "Default")
      (node (ref "JP4") (pin "8") (pinfunction "8_8") (pintype "passive"))
    )
    (net (code "65") (name "unconnected-(JP4-Pad10)") (class "Default")
      (node (ref "JP4") (pin "10") (pinfunction "10_10") (pintype "passive"))
    )
    (net (code "66") (name "unconnected-(JP4-Pad11)") (class "Default")
      (node (ref "JP4") (pin "11") (pinfunction "11_11") (pintype "passive"))
    )
    (net (code "67") (name "unconnected-(JP4-Pad12)") (class "Default")
      (node (ref "JP4") (pin "12") (pinfunction "12_12") (pintype "passive"))
    )
    (net (code "68") (name "unconnected-(JP4-Pad13)") (class "Default")
      (node (ref "JP4") (pin "13") (pinfunction "13_13") (pintype "passive"))
    )
    (net (code "69") (name "unconnected-(JP4-Pad14)") (class "Default")
      (node (ref "JP4") (pin "14") (pinfunction "14_14") (pintype "passive"))
    )
    (net (code "70") (name "unconnected-(JP4-Pad16)") (class "Default")
      (node (ref "JP4") (pin "16") (pinfunction "16_16") (pintype "passive"))
    )
    (net (code "71") (name "unconnected-(JP4-Pad17)") (class "Default")
      (node (ref "JP4") (pin "17") (pinfunction "17_17") (pintype "passive"))
    )
    (net (code "72") (name "unconnected-(JP4-Pad18)") (class "Default")
      (node (ref "JP4") (pin "18") (pinfunction "18_18") (pintype "passive"))
    )
    (net (code "73") (name "unconnected-(JP5-Pad3)") (class "Default")
      (node (ref "JP5") (pin "3") (pinfunction "3_3") (pintype "passive"))
    )
    (net (code "74") (name "unconnected-(JP5-Pad4)") (class "Default")
      (node (ref "JP5") (pin "4") (pinfunction "4_4") (pintype "passive"))
    )
    (net (code "75") (name "unconnected-(JP5-Pad6)") (class "Default")
      (node (ref "JP5") (pin "6") (pinfunction "6_6") (pintype "passive"))
    )
    (net (code "76") (name "unconnected-(JP5-Pad15)") (class "Default")
      (node (ref "JP5") (pin "15") (pinfunction "15_15") (pintype "passive"))
    )
    (net (code "77") (name "unconnected-(JP5-Pad19)") (class "Default")
      (node (ref "JP5") (pin "19") (pinfunction "19_19") (pintype "passive"))
    )
    (net (code "78") (name "unconnected-(SK7-SWITCH-PadP$2_SWITCH)") (class "Default")
      (node (ref "SK7") (pin "P$2_SWITCH") (pinfunction "SWITCH_P$2_SWITCH") (pintype "passive"))
    )
    (net (code "79") (name "unconnected-(SK8-SWITCH-PadP$2_SWITCH)") (class "Default")
      (node (ref "SK8") (pin "P$2_SWITCH") (pinfunction "SWITCH_P$2_SWITCH") (pintype "passive"))
    )
    (net (code "80") (name "unconnected-(SK9-SWITCH-PadP$2_SWITCH)") (class "Default")
      (node (ref "SK9") (pin "P$2_SWITCH") (pinfunction "SWITCH_P$2_SWITCH") (pintype "passive"))
    )
    (net (code "81") (name "unconnected-(SK10-SWITCH-PadP$2_SWITCH)") (class "Default")
      (node (ref "SK10") (pin "P$2_SWITCH") (pinfunction "SWITCH_P$2_SWITCH") (pintype "passive"))
    )
  )
)
